# Current-Sense-Sheet.net
KiCad netlist of a schematic drawn in Altium Designer
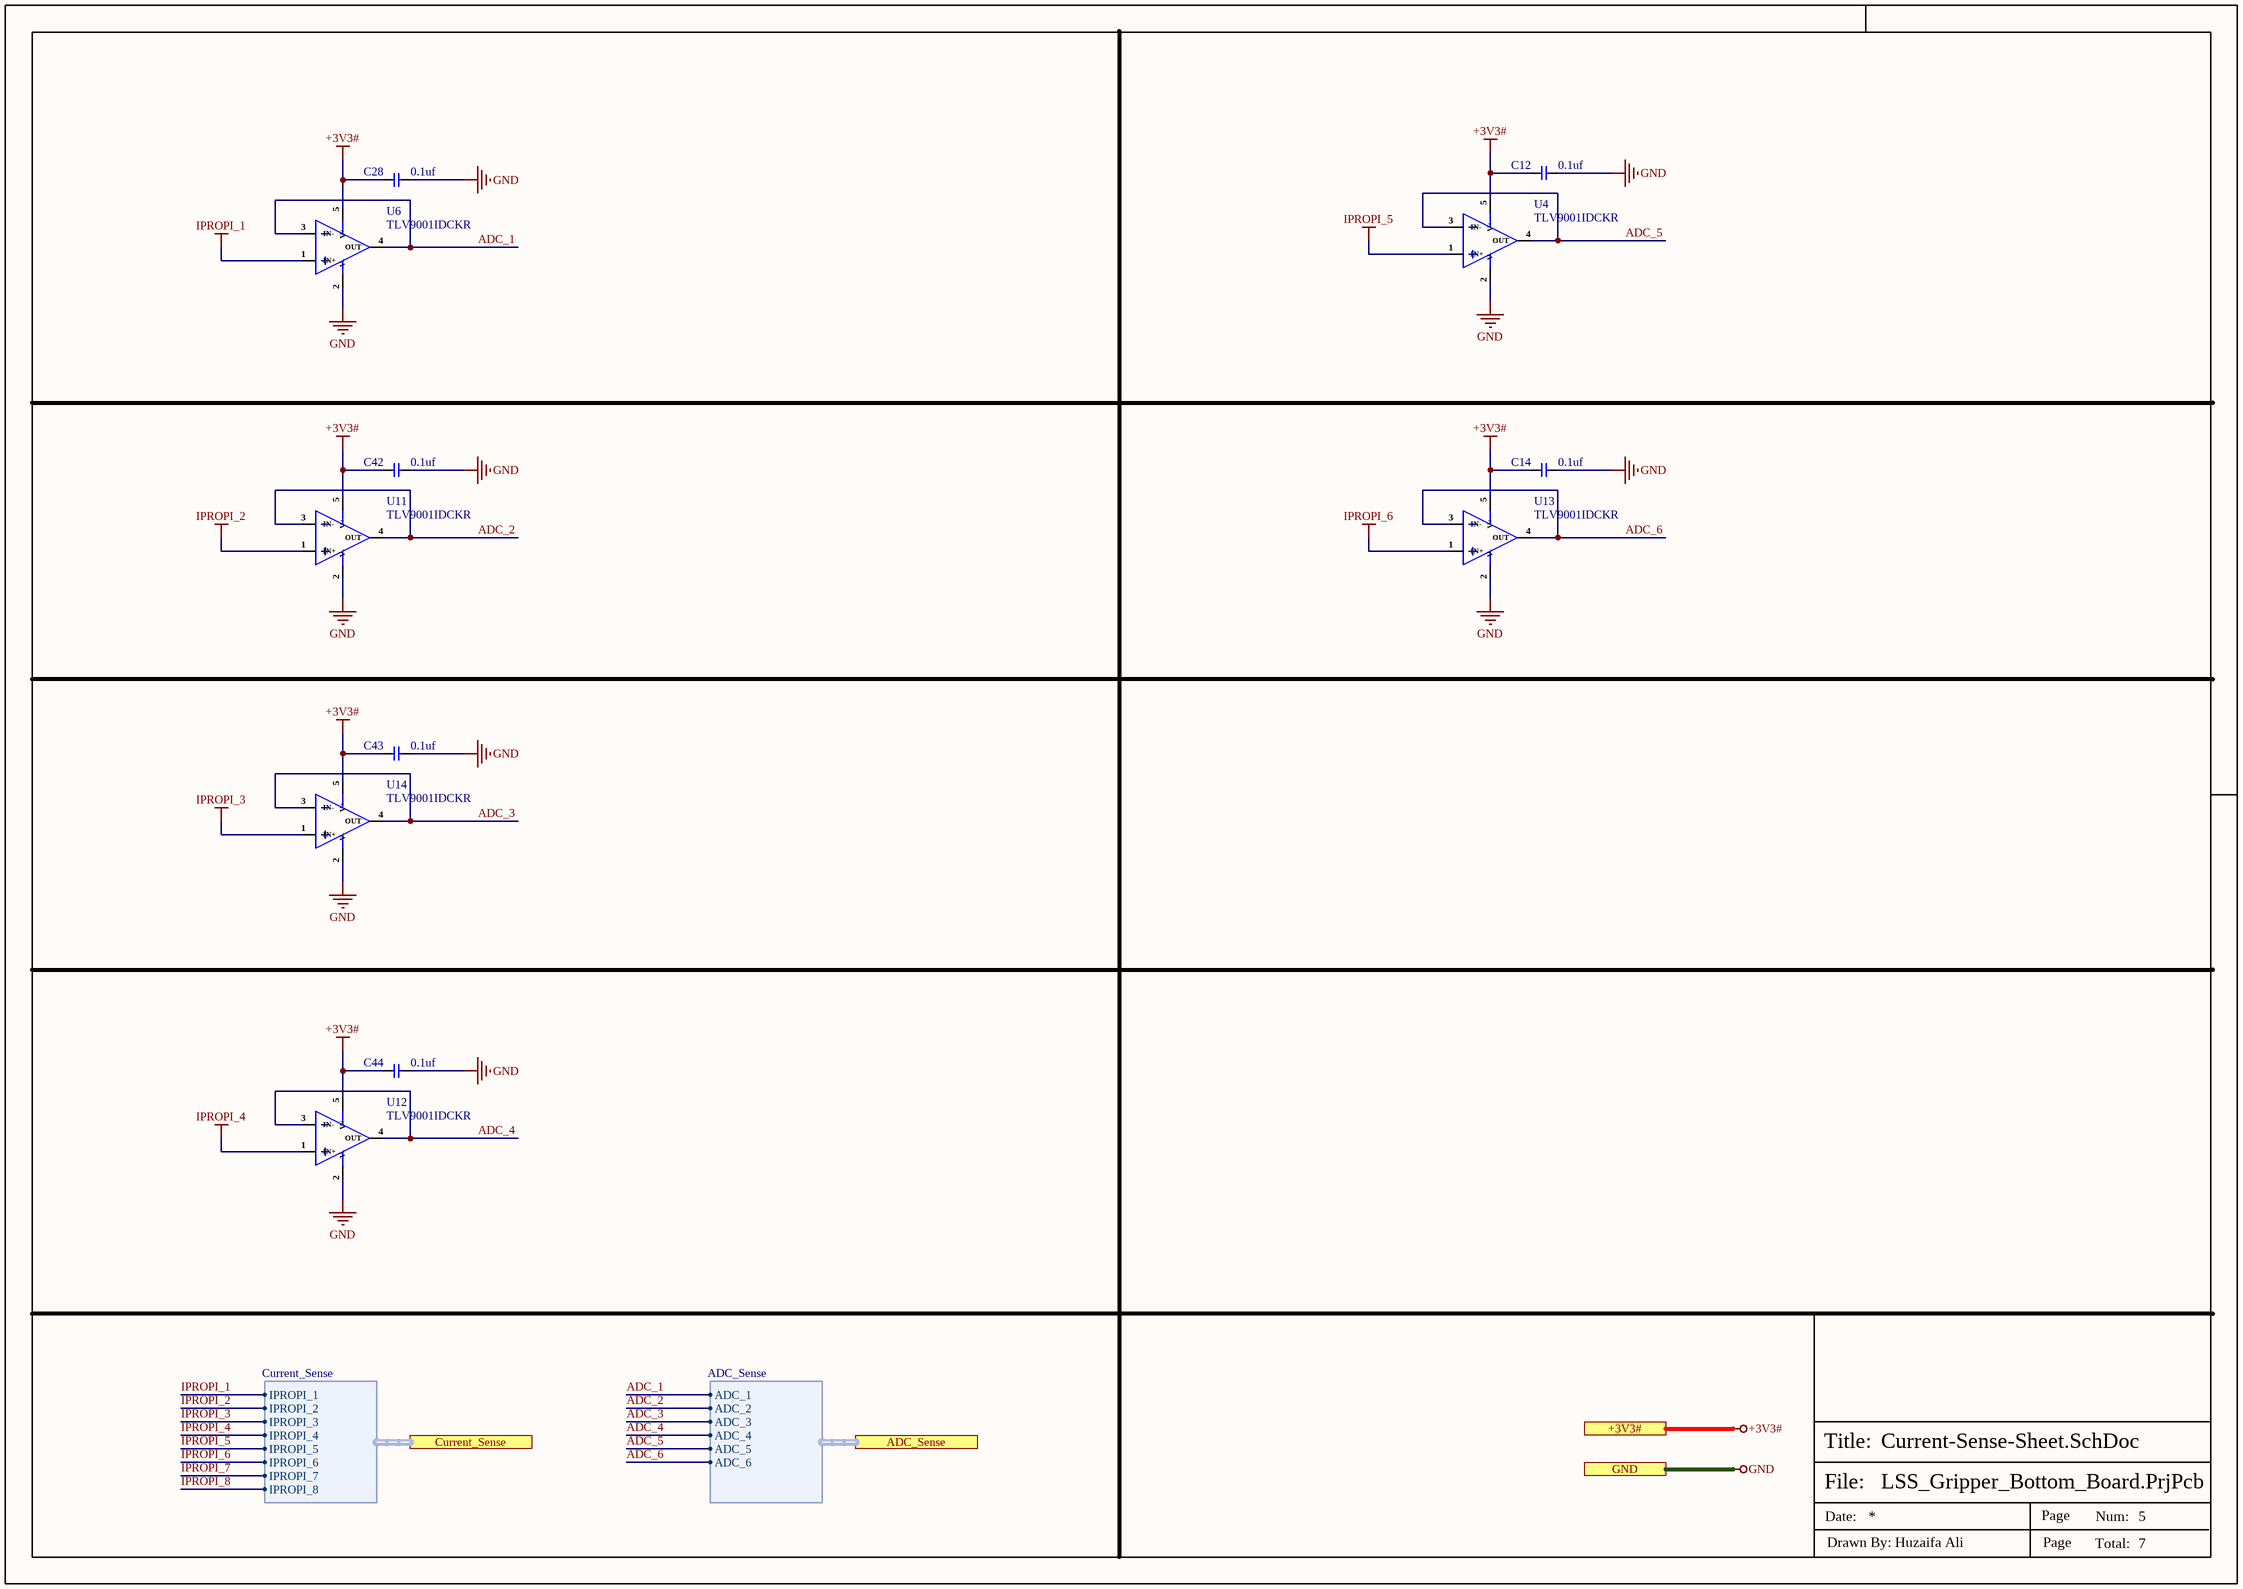
[diagram p0: Current-Sense-Sheet.SchDoc]

(export (version "E")
  (design (tool "Eeschema 10.0.6"))
  (components
    (comp (ref "C12")
      (value "0.1uf")
      (footprint "Cap-0402")
      (description "CAP CER 0.1UF 100V X5R 0402")
      (fields
        (field (name "MANUFACTURER") "Murata")
        (field (name "MANUFACTURER PART NUMBER") "GRM155R62A104KE14D")
      )
      (libsource (lib "eSpark Libraries") (part "GRM155R62A104KE14D"))
    )
    (comp (ref "C14")
      (value "0.1uf")
      (footprint "Cap-0402")
      (description "CAP CER 0.1UF 100V X5R 0402")
      (fields
        (field (name "MANUFACTURER") "Murata")
        (field (name "MANUFACTURER PART NUMBER") "GRM155R62A104KE14D")
      )
      (libsource (lib "eSpark Libraries") (part "GRM155R62A104KE14D"))
    )
    (comp (ref "C28")
      (value "0.1uf")
      (footprint "Cap-0402")
      (description "CAP CER 0.1UF 100V X5R 0402")
      (fields
        (field (name "MANUFACTURER") "Murata")
        (field (name "MANUFACTURER PART NUMBER") "GRM155R62A104KE14D")
      )
      (libsource (lib "eSpark Libraries") (part "GRM155R62A104KE14D"))
    )
    (comp (ref "C42")
      (value "0.1uf")
      (footprint "Cap-0402")
      (description "CAP CER 0.1UF 100V X5R 0402")
      (fields
        (field (name "MANUFACTURER") "Murata")
        (field (name "MANUFACTURER PART NUMBER") "GRM155R62A104KE14D")
      )
      (libsource (lib "eSpark Libraries") (part "GRM155R62A104KE14D"))
    )
    (comp (ref "C43")
      (value "0.1uf")
      (footprint "Cap-0402")
      (description "CAP CER 0.1UF 100V X5R 0402")
      (fields
        (field (name "MANUFACTURER") "Murata")
        (field (name "MANUFACTURER PART NUMBER") "GRM155R62A104KE14D")
      )
      (libsource (lib "eSpark Libraries") (part "GRM155R62A104KE14D"))
    )
    (comp (ref "C44")
      (value "0.1uf")
      (footprint "Cap-0402")
      (description "CAP CER 0.1UF 100V X5R 0402")
      (fields
        (field (name "MANUFACTURER") "Murata")
        (field (name "MANUFACTURER PART NUMBER") "GRM155R62A104KE14D")
      )
      (libsource (lib "eSpark Libraries") (part "GRM155R62A104KE14D"))
    )
    (comp (ref "U4")
      (value "TLV9001IDCKR")
      (footprint "SC-70-5")
      (description "IC CMOS 1 CIRCUIT SC70-5")
      (fields (field (name "MANUFACTURER") "Texas Instruments") (field (name "LCSC PART NUMBER") "C398362"))
      (libsource (lib "eSpark Libraries") (part "TLV9001IDCKR"))
    )
    (comp (ref "U6")
      (value "TLV9001IDCKR")
      (footprint "SC-70-5")
      (description "IC CMOS 1 CIRCUIT SC70-5")
      (fields (field (name "MANUFACTURER") "Texas Instruments") (field (name "LCSC PART NUMBER") "C398362"))
      (libsource (lib "eSpark Libraries") (part "TLV9001IDCKR"))
    )
    (comp (ref "U11")
      (value "TLV9001IDCKR")
      (footprint "SC-70-5")
      (description "IC CMOS 1 CIRCUIT SC70-5")
      (fields (field (name "MANUFACTURER") "Texas Instruments") (field (name "LCSC PART NUMBER") "C398362"))
      (libsource (lib "eSpark Libraries") (part "TLV9001IDCKR"))
    )
    (comp (ref "U12")
      (value "TLV9001IDCKR")
      (footprint "SC-70-5")
      (description "IC CMOS 1 CIRCUIT SC70-5")
      (fields (field (name "MANUFACTURER") "Texas Instruments") (field (name "LCSC PART NUMBER") "C398362"))
      (libsource (lib "eSpark Libraries") (part "TLV9001IDCKR"))
    )
    (comp (ref "U13")
      (value "TLV9001IDCKR")
      (footprint "SC-70-5")
      (description "IC CMOS 1 CIRCUIT SC70-5")
      (fields (field (name "MANUFACTURER") "Texas Instruments") (field (name "LCSC PART NUMBER") "C398362"))
      (libsource (lib "eSpark Libraries") (part "TLV9001IDCKR"))
    )
    (comp (ref "U14")
      (value "TLV9001IDCKR")
      (footprint "SC-70-5")
      (description "IC CMOS 1 CIRCUIT SC70-5")
      (fields (field (name "MANUFACTURER") "Texas Instruments") (field (name "LCSC PART NUMBER") "C398362"))
      (libsource (lib "eSpark Libraries") (part "TLV9001IDCKR"))
    )
  )
  (nets
    (net (code "3") (name "+3V3#") (class "Default")
      (node (ref "C12") (pin "1") (pinfunction "1_1") (pintype "passive"))
      (node (ref "C14") (pin "1") (pinfunction "1_1") (pintype "passive"))
      (node (ref "C28") (pin "1") (pinfunction "1_1") (pintype "passive"))
      (node (ref "C42") (pin "1") (pinfunction "1_1") (pintype "passive"))
      (node (ref "C43") (pin "1") (pinfunction "1_1") (pintype "passive"))
      (node (ref "C44") (pin "1") (pinfunction "1_1") (pintype "passive"))
      (node (ref "U11") (pin "5") (pinfunction "V+_5") (pintype "power_in"))
      (node (ref "U12") (pin "5") (pinfunction "V+_5") (pintype "power_in"))
      (node (ref "U13") (pin "5") (pinfunction "V+_5") (pintype "power_in"))
      (node (ref "U14") (pin "5") (pinfunction "V+_5") (pintype "power_in"))
      (node (ref "U4") (pin "5") (pinfunction "V+_5") (pintype "power_in"))
      (node (ref "U6") (pin "5") (pinfunction "V+_5") (pintype "power_in"))
    )
    (net (code "4") (name "/ADC_1") (class "Default")
      (node (ref "U6") (pin "3") (pinfunction "IN-_3") (pintype "passive"))
      (node (ref "U6") (pin "4") (pinfunction "OUT_4") (pintype "passive"))
    )
    (net (code "5") (name "/ADC_2") (class "Default")
      (node (ref "U11") (pin "3") (pinfunction "IN-_3") (pintype "passive"))
      (node (ref "U11") (pin "4") (pinfunction "OUT_4") (pintype "passive"))
    )
    (net (code "6") (name "/ADC_3") (class "Default")
      (node (ref "U14") (pin "3") (pinfunction "IN-_3") (pintype "passive"))
      (node (ref "U14") (pin "4") (pinfunction "OUT_4") (pintype "passive"))
    )
    (net (code "7") (name "/ADC_4") (class "Default")
      (node (ref "U12") (pin "3") (pinfunction "IN-_3") (pintype "passive"))
      (node (ref "U12") (pin "4") (pinfunction "OUT_4") (pintype "passive"))
    )
    (net (code "8") (name "/ADC_5") (class "Default")
      (node (ref "U4") (pin "3") (pinfunction "IN-_3") (pintype "passive"))
      (node (ref "U4") (pin "4") (pinfunction "OUT_4") (pintype "passive"))
    )
    (net (code "9") (name "/ADC_6") (class "Default")
      (node (ref "U13") (pin "3") (pinfunction "IN-_3") (pintype "passive"))
      (node (ref "U13") (pin "4") (pinfunction "OUT_4") (pintype "passive"))
    )
    (net (code "14") (name "GND") (class "Default")
      (node (ref "C12") (pin "2") (pinfunction "2_2") (pintype "passive"))
      (node (ref "C14") (pin "2") (pinfunction "2_2") (pintype "passive"))
      (node (ref "C28") (pin "2") (pinfunction "2_2") (pintype "passive"))
      (node (ref "C42") (pin "2") (pinfunction "2_2") (pintype "passive"))
      (node (ref "C43") (pin "2") (pinfunction "2_2") (pintype "passive"))
      (node (ref "C44") (pin "2") (pinfunction "2_2") (pintype "passive"))
      (node (ref "U11") (pin "2") (pinfunction "V-_2") (pintype "power_in"))
      (node (ref "U12") (pin "2") (pinfunction "V-_2") (pintype "power_in"))
      (node (ref "U13") (pin "2") (pinfunction "V-_2") (pintype "power_in"))
      (node (ref "U14") (pin "2") (pinfunction "V-_2") (pintype "power_in"))
      (node (ref "U4") (pin "2") (pinfunction "V-_2") (pintype "power_in"))
      (node (ref "U6") (pin "2") (pinfunction "V-_2") (pintype "power_in"))
    )
    (net (code "15") (name "IPROPI_1") (class "Default")
      (node (ref "U6") (pin "1") (pinfunction "IN+_1") (pintype "passive"))
    )
    (net (code "16") (name "IPROPI_2") (class "Default")
      (node (ref "U11") (pin "1") (pinfunction "IN+_1") (pintype "passive"))
    )
    (net (code "17") (name "IPROPI_3") (class "Default")
      (node (ref "U14") (pin "1") (pinfunction "IN+_1") (pintype "passive"))
    )
    (net (code "18") (name "IPROPI_4") (class "Default")
      (node (ref "U12") (pin "1") (pinfunction "IN+_1") (pintype "passive"))
    )
    (net (code "19") (name "IPROPI_5") (class "Default")
      (node (ref "U4") (pin "1") (pinfunction "IN+_1") (pintype "passive"))
    )
    (net (code "20") (name "IPROPI_6") (class "Default")
      (node (ref "U13") (pin "1") (pinfunction "IN+_1") (pintype "passive"))
    )
  )
)
